# ESP_8266.net
KiCad netlist of a schematic drawn in Altium Designer
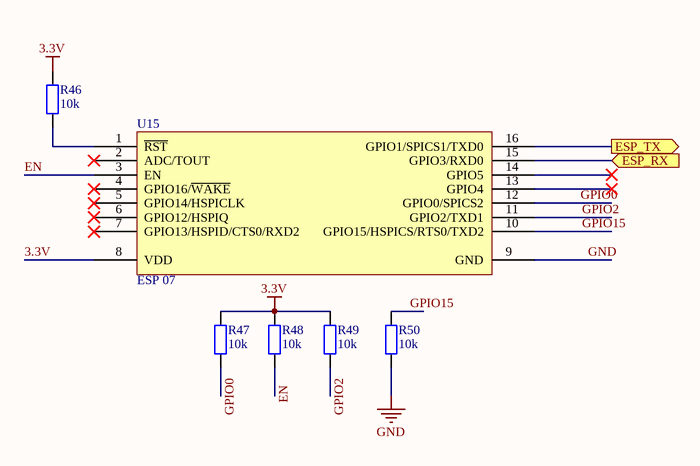
[diagram p0: ESP_8266.SchDoc]

(export (version "E")
  (design (tool "Eeschema 10.0.6"))
  (components
    (comp (ref "R46")
      (value "10k")
      (footprint "tro smd 0805")
      (description "Dán")
      (libsource (lib "Altium_Lib_by_KhueNguyenCreator") (part "Tro 0805 1% 10k"))
    )
    (comp (ref "R47")
      (value "10k")
      (footprint "tro smd 0805")
      (description "Dán")
      (libsource (lib "Altium_Lib_by_KhueNguyenCreator") (part "Tro 0805 1% 10k"))
    )
    (comp (ref "R48")
      (value "10k")
      (footprint "tro smd 0805")
      (description "Dán")
      (libsource (lib "Altium_Lib_by_KhueNguyenCreator") (part "Tro 0805 1% 10k"))
    )
    (comp (ref "R49")
      (value "10k")
      (footprint "tro smd 0805")
      (description "Dán")
      (libsource (lib "Altium_Lib_by_KhueNguyenCreator") (part "Tro 0805 1% 10k"))
    )
    (comp (ref "R50")
      (value "10k")
      (footprint "tro smd 0805")
      (description "Dán")
      (libsource (lib "Altium_Lib_by_KhueNguyenCreator") (part "Tro 0805 1% 10k"))
    )
    (comp (ref "U15")
      (value "ESP 07")
      (footprint "ESP8266 07")
      (description "ESP8266 07 16 Pin")
      (libsource (lib "Altium_Lib_by_KhueNguyenCreator") (part "ESP8266 07"))
    )
  )
  (nets
    (net (code "1") (name "/EN") (class "Default")
      (node (ref "R48") (pin "1") (pinfunction "1_1") (pintype "passive"))
      (node (ref "U15") (pin "3") (pinfunction "EN_3") (pintype "passive"))
    )
    (net (code "2") (name "/ESP_RX") (class "Default")
      (node (ref "U15") (pin "15") (pinfunction "GPIO3/RXD0_15") (pintype "passive"))
    )
    (net (code "3") (name "/ESP_TX") (class "Default")
      (node (ref "U15") (pin "16") (pinfunction "GPIO1/SPICS1/TXD0_16") (pintype "passive"))
    )
    (net (code "4") (name "/GPIO0") (class "Default")
      (node (ref "R47") (pin "1") (pinfunction "1_1") (pintype "passive"))
      (node (ref "U15") (pin "12") (pinfunction "GPIO0/SPICS2_12") (pintype "passive"))
    )
    (net (code "5") (name "/GPIO2") (class "Default")
      (node (ref "R49") (pin "1") (pinfunction "1_1") (pintype "passive"))
      (node (ref "U15") (pin "11") (pinfunction "GPIO2/TXD1_11") (pintype "passive"))
    )
    (net (code "6") (name "/GPIO15") (class "Default")
      (node (ref "R50") (pin "2") (pinfunction "2_2") (pintype "passive"))
      (node (ref "U15") (pin "10") (pinfunction "GPIO15/HSPICS/RTS0/TXD2_10") (pintype "passive"))
    )
    (net (code "7") (name "3.3V") (class "Default")
      (node (ref "R46") (pin "2") (pinfunction "2_2") (pintype "passive"))
      (node (ref "R47") (pin "2") (pinfunction "2_2") (pintype "passive"))
      (node (ref "R48") (pin "2") (pinfunction "2_2") (pintype "passive"))
      (node (ref "R49") (pin "2") (pinfunction "2_2") (pintype "passive"))
      (node (ref "U15") (pin "8") (pinfunction "VDD_8") (pintype "passive"))
    )
    (net (code "8") (name "GND") (class "Default")
      (node (ref "R50") (pin "1") (pinfunction "1_1") (pintype "passive"))
      (node (ref "U15") (pin "9") (pinfunction "GND_9") (pintype "passive"))
    )
    (net (code "9") (name "Net-(U15-~{RST})") (class "Default")
      (node (ref "R46") (pin "1") (pinfunction "1_1") (pintype "passive"))
      (node (ref "U15") (pin "1") (pinfunction "~{RST}_1") (pintype "passive"))
    )
    (net (code "10") (name "unconnected-(U15-ADC{slash}TOUT-Pad2)") (class "Default")
      (node (ref "U15") (pin "2") (pinfunction "ADC/TOUT_2") (pintype "passive+no_connect"))
    )
    (net (code "11") (name "unconnected-(U15-GPIO4-Pad13)") (class "Default")
      (node (ref "U15") (pin "13") (pinfunction "GPIO4_13") (pintype "passive+no_connect"))
    )
    (net (code "12") (name "unconnected-(U15-GPIO5-Pad14)") (class "Default")
      (node (ref "U15") (pin "14") (pinfunction "GPIO5_14") (pintype "passive+no_connect"))
    )
    (net (code "13") (name "unconnected-(U15-GPIO12{slash}HSPIQ-Pad6)") (class "Default")
      (node (ref "U15") (pin "6") (pinfunction "GPIO12/HSPIQ_6") (pintype "passive+no_connect"))
    )
    (net (code "14") (name "unconnected-(U15-GPIO13{slash}HSPID{slash}CTS0{slash}RXD2-Pad7)") (class "Default")
      (node (ref "U15") (pin "7") (pinfunction "GPIO13/HSPID/CTS0/RXD2_7") (pintype "passive+no_connect"))
    )
    (net (code "15") (name "unconnected-(U15-GPIO14{slash}HSPICLK-Pad5)") (class "Default")
      (node (ref "U15") (pin "5") (pinfunction "GPIO14/HSPICLK_5") (pintype "passive+no_connect"))
    )
    (net (code "16") (name "unconnected-(U15-GPIO16{slash}~{WAKE}-Pad4)") (class "Default")
      (node (ref "U15") (pin "4") (pinfunction "GPIO16/~{WAKE}_4") (pintype "passive+no_connect"))
    )
  )
)
